# ProtoShield_V4_0.net
KiCad netlist of a schematic drawn in EAGLE
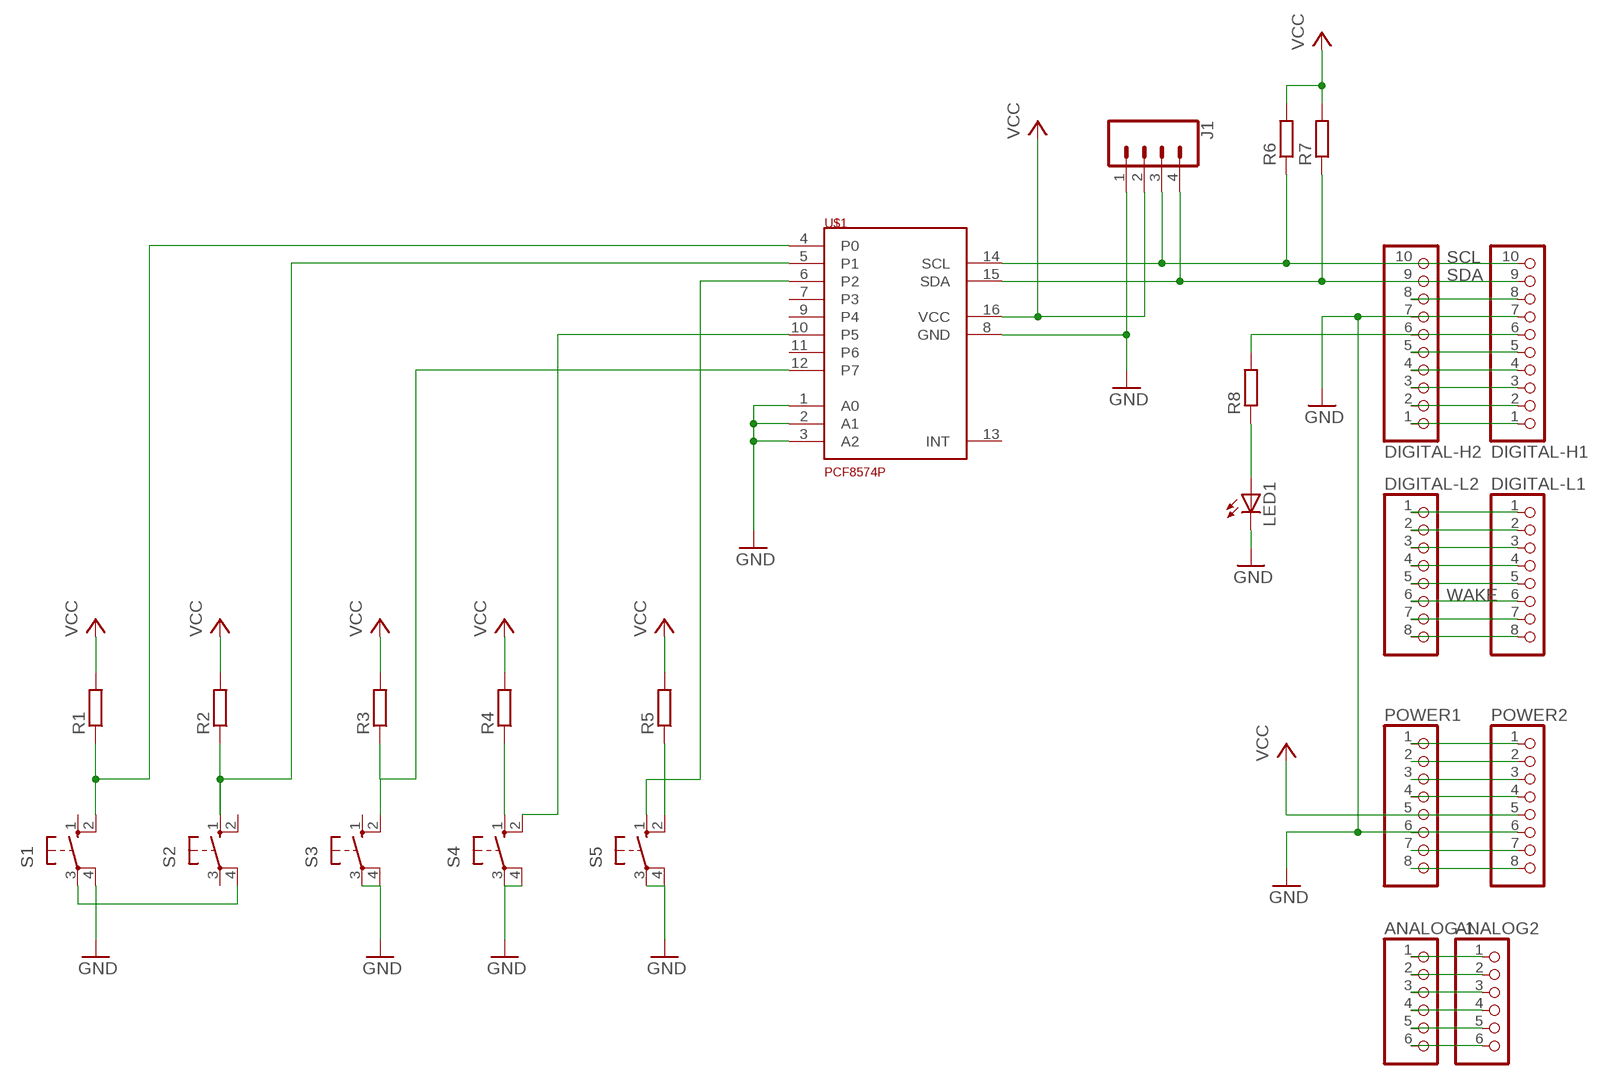
[diagram p0: schematic, sheet 1]

(export (version "E")
  (design (tool "Eeschema 10.0.6"))
  (components
    (comp (ref "ANALOG-1")
      (value "PINHD-1X6")
      (footprint "eagle-import:1X06")
      (libsource (lib "eagle-import") (part "PINHD-1X6"))
    )
    (comp (ref "ANALOG2")
      (value "PINHD-1X6")
      (footprint "eagle-import:1X06")
      (libsource (lib "eagle-import") (part "PINHD-1X6"))
    )
    (comp (ref "DIGITAL-H1")
      (value "PINHD-1X10TH")
      (footprint "eagle-import:1X10-TH")
      (libsource (lib "eagle-import") (part "PINHD-1X10TH"))
    )
    (comp (ref "DIGITAL-H2")
      (value "PINHD-1X10TH")
      (footprint "eagle-import:1X10-TH")
      (libsource (lib "eagle-import") (part "PINHD-1X10TH"))
    )
    (comp (ref "DIGITAL-L1")
      (value "PINHD-1X8")
      (footprint "eagle-import:1X08")
      (fields (field (name "MF") "EPCOS") (field (name "MPN") "B67345B0001X087"))
      (libsource (lib "eagle-import") (part "pinhead_PINHD-1X8"))
    )
    (comp (ref "DIGITAL-L2")
      (value "PINHD-1X8")
      (footprint "eagle-import:1X08")
      (fields (field (name "MF") "EPCOS") (field (name "MPN") "B67345B0001X087"))
      (libsource (lib "eagle-import") (part "pinhead_PINHD-1X8"))
    )
    (comp (ref "J1")
      (value "CONN_04PTH")
      (footprint "eagle-import:1X04")
      (libsource (lib "eagle-import") (part "CONN_04PTH"))
    )
    (comp (ref "LED1")
      (value "LED3MM")
      (footprint "eagle-import:LED3MM")
      (libsource (lib "eagle-import") (part "LED3MM"))
    )
    (comp (ref "POWER1")
      (value "PINHD-1X8TH")
      (footprint "eagle-import:1X08-TH")
      (libsource (lib "eagle-import") (part "PINHD-1X8TH"))
    )
    (comp (ref "POWER2")
      (value "PINHD-1X8TH")
      (footprint "eagle-import:1X08-TH")
      (libsource (lib "eagle-import") (part "PINHD-1X8TH"))
    )
    (comp (ref "R1")
      (value "R-EU_0207/10")
      (footprint "eagle-import:0207_10")
      (libsource (lib "eagle-import") (part "R-EU_0207/10"))
    )
    (comp (ref "R2")
      (value "R-EU_0207/10")
      (footprint "eagle-import:0207_10")
      (libsource (lib "eagle-import") (part "R-EU_0207/10"))
    )
    (comp (ref "R3")
      (value "R-EU_0207/10")
      (footprint "eagle-import:0207_10")
      (libsource (lib "eagle-import") (part "R-EU_0207/10"))
    )
    (comp (ref "R4")
      (value "R-EU_0207/10")
      (footprint "eagle-import:0207_10")
      (libsource (lib "eagle-import") (part "R-EU_0207/10"))
    )
    (comp (ref "R5")
      (value "R-EU_0207/10")
      (footprint "eagle-import:0207_10")
      (libsource (lib "eagle-import") (part "R-EU_0207/10"))
    )
    (comp (ref "R6")
      (value "R-EU_0207/10")
      (footprint "eagle-import:0207_10")
      (libsource (lib "eagle-import") (part "R-EU_0207/10"))
    )
    (comp (ref "R7")
      (value "R-EU_0207/10")
      (footprint "eagle-import:0207_10")
      (libsource (lib "eagle-import") (part "R-EU_0207/10"))
    )
    (comp (ref "R8")
      (value "R-EU_0207/10")
      (footprint "eagle-import:0207_10")
      (libsource (lib "eagle-import") (part "R-EU_0207/10"))
    )
    (comp (ref "S1")
      (value "10-XX")
      (footprint "eagle-import:B3F-10XX")
      (fields (field (name "MPN") "B3F-1000"))
      (libsource (lib "eagle-import") (part "10-XX"))
    )
    (comp (ref "S2")
      (value "10-XX")
      (footprint "eagle-import:B3F-10XX")
      (fields (field (name "MPN") "B3F-1000"))
      (libsource (lib "eagle-import") (part "10-XX"))
    )
    (comp (ref "S3")
      (value "10-XX")
      (footprint "eagle-import:B3F-10XX")
      (fields (field (name "MPN") "B3F-1000"))
      (libsource (lib "eagle-import") (part "10-XX"))
    )
    (comp (ref "S4")
      (value "10-XX")
      (footprint "eagle-import:B3F-10XX")
      (fields (field (name "MPN") "B3F-1000"))
      (libsource (lib "eagle-import") (part "10-XX"))
    )
    (comp (ref "S5")
      (value "10-XX")
      (footprint "eagle-import:B3F-10XX")
      (fields (field (name "MPN") "B3F-1000"))
      (libsource (lib "eagle-import") (part "10-XX"))
    )
    (comp (ref "U$1")
      (value "PCF8574P")
      (footprint "eagle-import:DIL16")
      (libsource (lib "eagle-import") (part "PCF8574P"))
    )
  )
  (nets
    (net (code "1") (name "/SCL") (class "Default")
      (node (ref "DIGITAL-H1") (pin "10") (pinfunction "10_10") (pintype "passive"))
      (node (ref "DIGITAL-H2") (pin "10") (pinfunction "10_10") (pintype "passive"))
      (node (ref "J1") (pin "3") (pinfunction "3_3") (pintype "passive"))
      (node (ref "R6") (pin "1") (pinfunction "1_1") (pintype "passive"))
      (node (ref "U$1") (pin "14") (pinfunction "SCL_14") (pintype "bidirectional"))
    )
    (net (code "2") (name "/SDA") (class "Default")
      (node (ref "DIGITAL-H1") (pin "9") (pinfunction "9_9") (pintype "passive"))
      (node (ref "DIGITAL-H2") (pin "9") (pinfunction "9_9") (pintype "passive"))
      (node (ref "J1") (pin "4") (pinfunction "4_4") (pintype "passive"))
      (node (ref "R7") (pin "1") (pinfunction "1_1") (pintype "passive"))
      (node (ref "U$1") (pin "15") (pinfunction "SDA_15") (pintype "bidirectional"))
    )
    (net (code "3") (name "/WAKE") (class "Default")
      (node (ref "DIGITAL-L1") (pin "6") (pinfunction "6_6") (pintype "passive"))
      (node (ref "DIGITAL-L2") (pin "6") (pinfunction "6_6") (pintype "passive"))
    )
    (net (code "4") (name "GND") (class "Default")
      (node (ref "DIGITAL-H1") (pin "7") (pinfunction "7_7") (pintype "passive"))
      (node (ref "DIGITAL-H2") (pin "7") (pinfunction "7_7") (pintype "passive"))
      (node (ref "J1") (pin "1") (pinfunction "1_1") (pintype "passive"))
      (node (ref "LED1") (pin "K") (pinfunction "C_K") (pintype "passive"))
      (node (ref "POWER1") (pin "6") (pinfunction "6_6") (pintype "passive"))
      (node (ref "POWER2") (pin "6") (pinfunction "6_6") (pintype "passive"))
      (node (ref "S1") (pin "4") (pinfunction "P1_4") (pintype "passive"))
      (node (ref "S3") (pin "3") (pinfunction "P_3") (pintype "passive"))
      (node (ref "S3") (pin "4") (pinfunction "P1_4") (pintype "passive"))
      (node (ref "S4") (pin "3") (pinfunction "P_3") (pintype "passive"))
      (node (ref "S4") (pin "4") (pinfunction "P1_4") (pintype "passive"))
      (node (ref "S5") (pin "3") (pinfunction "P_3") (pintype "passive"))
      (node (ref "S5") (pin "4") (pinfunction "P1_4") (pintype "passive"))
      (node (ref "U$1") (pin "1") (pinfunction "A0_1") (pintype "bidirectional"))
      (node (ref "U$1") (pin "2") (pinfunction "A1_2") (pintype "bidirectional"))
      (node (ref "U$1") (pin "3") (pinfunction "A2_3") (pintype "bidirectional"))
      (node (ref "U$1") (pin "8") (pinfunction "GND_8") (pintype "bidirectional"))
    )
    (net (code "5") (name "Net-(ANALOG-1-Pad1)") (class "Default")
      (node (ref "ANALOG-1") (pin "1") (pinfunction "1_1") (pintype "passive"))
      (node (ref "ANALOG2") (pin "1") (pinfunction "1_1") (pintype "passive"))
    )
    (net (code "6") (name "Net-(ANALOG-1-Pad2)") (class "Default")
      (node (ref "ANALOG-1") (pin "2") (pinfunction "2_2") (pintype "passive"))
      (node (ref "ANALOG2") (pin "2") (pinfunction "2_2") (pintype "passive"))
    )
    (net (code "7") (name "Net-(ANALOG-1-Pad3)") (class "Default")
      (node (ref "ANALOG-1") (pin "3") (pinfunction "3_3") (pintype "passive"))
      (node (ref "ANALOG2") (pin "3") (pinfunction "3_3") (pintype "passive"))
    )
    (net (code "8") (name "Net-(ANALOG-1-Pad4)") (class "Default")
      (node (ref "ANALOG-1") (pin "4") (pinfunction "4_4") (pintype "passive"))
      (node (ref "ANALOG2") (pin "4") (pinfunction "4_4") (pintype "passive"))
    )
    (net (code "9") (name "Net-(ANALOG-1-Pad5)") (class "Default")
      (node (ref "ANALOG-1") (pin "5") (pinfunction "5_5") (pintype "passive"))
      (node (ref "ANALOG2") (pin "5") (pinfunction "5_5") (pintype "passive"))
    )
    (net (code "10") (name "Net-(ANALOG-1-Pad6)") (class "Default")
      (node (ref "ANALOG-1") (pin "6") (pinfunction "6_6") (pintype "passive"))
      (node (ref "ANALOG2") (pin "6") (pinfunction "6_6") (pintype "passive"))
    )
    (net (code "11") (name "Net-(DIGITAL-H1-Pad1)") (class "Default")
      (node (ref "DIGITAL-H1") (pin "1") (pinfunction "1_1") (pintype "passive"))
      (node (ref "DIGITAL-H2") (pin "1") (pinfunction "1_1") (pintype "passive"))
    )
    (net (code "12") (name "Net-(DIGITAL-H1-Pad2)") (class "Default")
      (node (ref "DIGITAL-H1") (pin "2") (pinfunction "2_2") (pintype "passive"))
      (node (ref "DIGITAL-H2") (pin "2") (pinfunction "2_2") (pintype "passive"))
    )
    (net (code "13") (name "Net-(DIGITAL-H1-Pad3)") (class "Default")
      (node (ref "DIGITAL-H1") (pin "3") (pinfunction "3_3") (pintype "passive"))
      (node (ref "DIGITAL-H2") (pin "3") (pinfunction "3_3") (pintype "passive"))
    )
    (net (code "14") (name "Net-(DIGITAL-H1-Pad4)") (class "Default")
      (node (ref "DIGITAL-H1") (pin "4") (pinfunction "4_4") (pintype "passive"))
      (node (ref "DIGITAL-H2") (pin "4") (pinfunction "4_4") (pintype "passive"))
    )
    (net (code "15") (name "Net-(DIGITAL-H1-Pad5)") (class "Default")
      (node (ref "DIGITAL-H1") (pin "5") (pinfunction "5_5") (pintype "passive"))
      (node (ref "DIGITAL-H2") (pin "5") (pinfunction "5_5") (pintype "passive"))
    )
    (net (code "16") (name "Net-(DIGITAL-H1-Pad6)") (class "Default")
      (node (ref "DIGITAL-H1") (pin "6") (pinfunction "6_6") (pintype "passive"))
      (node (ref "DIGITAL-H2") (pin "6") (pinfunction "6_6") (pintype "passive"))
      (node (ref "R8") (pin "2") (pinfunction "2_2") (pintype "passive"))
    )
    (net (code "17") (name "Net-(DIGITAL-H1-Pad8)") (class "Default")
      (node (ref "DIGITAL-H1") (pin "8") (pinfunction "8_8") (pintype "passive"))
      (node (ref "DIGITAL-H2") (pin "8") (pinfunction "8_8") (pintype "passive"))
    )
    (net (code "18") (name "Net-(DIGITAL-L1-Pad1)") (class "Default")
      (node (ref "DIGITAL-L1") (pin "1") (pinfunction "1_1") (pintype "passive"))
      (node (ref "DIGITAL-L2") (pin "1") (pinfunction "1_1") (pintype "passive"))
    )
    (net (code "19") (name "Net-(DIGITAL-L1-Pad2)") (class "Default")
      (node (ref "DIGITAL-L1") (pin "2") (pinfunction "2_2") (pintype "passive"))
      (node (ref "DIGITAL-L2") (pin "2") (pinfunction "2_2") (pintype "passive"))
    )
    (net (code "20") (name "Net-(DIGITAL-L1-Pad3)") (class "Default")
      (node (ref "DIGITAL-L1") (pin "3") (pinfunction "3_3") (pintype "passive"))
      (node (ref "DIGITAL-L2") (pin "3") (pinfunction "3_3") (pintype "passive"))
    )
    (net (code "21") (name "Net-(DIGITAL-L1-Pad4)") (class "Default")
      (node (ref "DIGITAL-L1") (pin "4") (pinfunction "4_4") (pintype "passive"))
      (node (ref "DIGITAL-L2") (pin "4") (pinfunction "4_4") (pintype "passive"))
    )
    (net (code "22") (name "Net-(DIGITAL-L1-Pad5)") (class "Default")
      (node (ref "DIGITAL-L1") (pin "5") (pinfunction "5_5") (pintype "passive"))
      (node (ref "DIGITAL-L2") (pin "5") (pinfunction "5_5") (pintype "passive"))
    )
    (net (code "23") (name "Net-(DIGITAL-L1-Pad7)") (class "Default")
      (node (ref "DIGITAL-L1") (pin "7") (pinfunction "7_7") (pintype "passive"))
      (node (ref "DIGITAL-L2") (pin "7") (pinfunction "7_7") (pintype "passive"))
    )
    (net (code "24") (name "Net-(DIGITAL-L1-Pad8)") (class "Default")
      (node (ref "DIGITAL-L1") (pin "8") (pinfunction "8_8") (pintype "passive"))
      (node (ref "DIGITAL-L2") (pin "8") (pinfunction "8_8") (pintype "passive"))
    )
    (net (code "25") (name "Net-(LED1-PadA)") (class "Default")
      (node (ref "LED1") (pin "A") (pinfunction "A_A") (pintype "passive"))
      (node (ref "R8") (pin "1") (pinfunction "1_1") (pintype "passive"))
    )
    (net (code "26") (name "Net-(POWER1-Pad1)") (class "Default")
      (node (ref "POWER1") (pin "1") (pinfunction "1_1") (pintype "passive"))
      (node (ref "POWER2") (pin "1") (pinfunction "1_1") (pintype "passive"))
    )
    (net (code "27") (name "Net-(POWER1-Pad2)") (class "Default")
      (node (ref "POWER1") (pin "2") (pinfunction "2_2") (pintype "passive"))
      (node (ref "POWER2") (pin "2") (pinfunction "2_2") (pintype "passive"))
    )
    (net (code "28") (name "Net-(POWER1-Pad3)") (class "Default")
      (node (ref "POWER1") (pin "3") (pinfunction "3_3") (pintype "passive"))
      (node (ref "POWER2") (pin "3") (pinfunction "3_3") (pintype "passive"))
    )
    (net (code "29") (name "Net-(POWER1-Pad4)") (class "Default")
      (node (ref "POWER1") (pin "4") (pinfunction "4_4") (pintype "passive"))
      (node (ref "POWER2") (pin "4") (pinfunction "4_4") (pintype "passive"))
    )
    (net (code "30") (name "Net-(POWER1-Pad7)") (class "Default")
      (node (ref "POWER1") (pin "7") (pinfunction "7_7") (pintype "passive"))
      (node (ref "POWER2") (pin "7") (pinfunction "7_7") (pintype "passive"))
    )
    (net (code "31") (name "Net-(POWER1-Pad8)") (class "Default")
      (node (ref "POWER1") (pin "8") (pinfunction "8_8") (pintype "passive"))
      (node (ref "POWER2") (pin "8") (pinfunction "8_8") (pintype "passive"))
    )
    (net (code "32") (name "Net-(S1-P)") (class "Default")
      (node (ref "S1") (pin "3") (pinfunction "P_3") (pintype "passive"))
      (node (ref "S2") (pin "4") (pinfunction "P1_4") (pintype "passive"))
    )
    (net (code "33") (name "Net-(S1-S1)") (class "Default")
      (node (ref "R1") (pin "1") (pinfunction "1_1") (pintype "passive"))
      (node (ref "S1") (pin "2") (pinfunction "S1_2") (pintype "passive"))
      (node (ref "U$1") (pin "4") (pinfunction "P0_4") (pintype "bidirectional"))
    )
    (net (code "34") (name "Net-(S2-S)") (class "Default")
      (node (ref "R2") (pin "1") (pinfunction "1_1") (pintype "passive"))
      (node (ref "S2") (pin "1") (pinfunction "S_1") (pintype "passive"))
      (node (ref "U$1") (pin "5") (pinfunction "P1_5") (pintype "bidirectional"))
    )
    (net (code "35") (name "Net-(S3-S1)") (class "Default")
      (node (ref "R3") (pin "1") (pinfunction "1_1") (pintype "passive"))
      (node (ref "S3") (pin "2") (pinfunction "S1_2") (pintype "passive"))
      (node (ref "U$1") (pin "12") (pinfunction "P7_12") (pintype "bidirectional"))
    )
    (net (code "36") (name "Net-(S4-S)") (class "Default")
      (node (ref "R4") (pin "1") (pinfunction "1_1") (pintype "passive"))
      (node (ref "S4") (pin "1") (pinfunction "S_1") (pintype "passive"))
    )
    (net (code "37") (name "Net-(S4-S1)") (class "Default")
      (node (ref "S4") (pin "2") (pinfunction "S1_2") (pintype "passive"))
      (node (ref "U$1") (pin "10") (pinfunction "P5_10") (pintype "bidirectional"))
    )
    (net (code "38") (name "Net-(S5-S)") (class "Default")
      (node (ref "S5") (pin "1") (pinfunction "S_1") (pintype "passive"))
      (node (ref "U$1") (pin "6") (pinfunction "P2_6") (pintype "bidirectional"))
    )
    (net (code "39") (name "Net-(S5-S1)") (class "Default")
      (node (ref "R5") (pin "1") (pinfunction "1_1") (pintype "passive"))
      (node (ref "S5") (pin "2") (pinfunction "S1_2") (pintype "passive"))
    )
    (net (code "40") (name "VCC") (class "Default")
      (node (ref "J1") (pin "2") (pinfunction "2_2") (pintype "passive"))
      (node (ref "POWER1") (pin "5") (pinfunction "5_5") (pintype "passive"))
      (node (ref "POWER2") (pin "5") (pinfunction "5_5") (pintype "passive"))
      (node (ref "R1") (pin "2") (pinfunction "2_2") (pintype "passive"))
      (node (ref "R2") (pin "2") (pinfunction "2_2") (pintype "passive"))
      (node (ref "R3") (pin "2") (pinfunction "2_2") (pintype "passive"))
      (node (ref "R4") (pin "2") (pinfunction "2_2") (pintype "passive"))
      (node (ref "R5") (pin "2") (pinfunction "2_2") (pintype "passive"))
      (node (ref "R6") (pin "2") (pinfunction "2_2") (pintype "passive"))
      (node (ref "R7") (pin "2") (pinfunction "2_2") (pintype "passive"))
      (node (ref "U$1") (pin "16") (pinfunction "VCC_16") (pintype "bidirectional"))
    )
    (net (code "41") (name "unconnected-(S1-S-Pad1)") (class "Default")
      (node (ref "S1") (pin "1") (pinfunction "S_1") (pintype "passive"))
    )
    (net (code "42") (name "unconnected-(S2-P-Pad3)") (class "Default")
      (node (ref "S2") (pin "3") (pinfunction "P_3") (pintype "passive"))
    )
    (net (code "43") (name "unconnected-(S2-S1-Pad2)") (class "Default")
      (node (ref "S2") (pin "2") (pinfunction "S1_2") (pintype "passive"))
    )
    (net (code "44") (name "unconnected-(S3-S-Pad1)") (class "Default")
      (node (ref "S3") (pin "1") (pinfunction "S_1") (pintype "passive"))
    )
    (net (code "45") (name "unconnected-(U$1-INT-Pad13)") (class "Default")
      (node (ref "U$1") (pin "13") (pinfunction "INT_13") (pintype "bidirectional"))
    )
    (net (code "46") (name "unconnected-(U$1-P3-Pad7)") (class "Default")
      (node (ref "U$1") (pin "7") (pinfunction "P3_7") (pintype "bidirectional"))
    )
    (net (code "47") (name "unconnected-(U$1-P4-Pad9)") (class "Default")
      (node (ref "U$1") (pin "9") (pinfunction "P4_9") (pintype "bidirectional"))
    )
    (net (code "48") (name "unconnected-(U$1-P6-Pad11)") (class "Default")
      (node (ref "U$1") (pin "11") (pinfunction "P6_11") (pintype "bidirectional"))
    )
  )
)
